# Restaurant-RFID-System.net
KiCad netlist of a schematic drawn in EAGLE
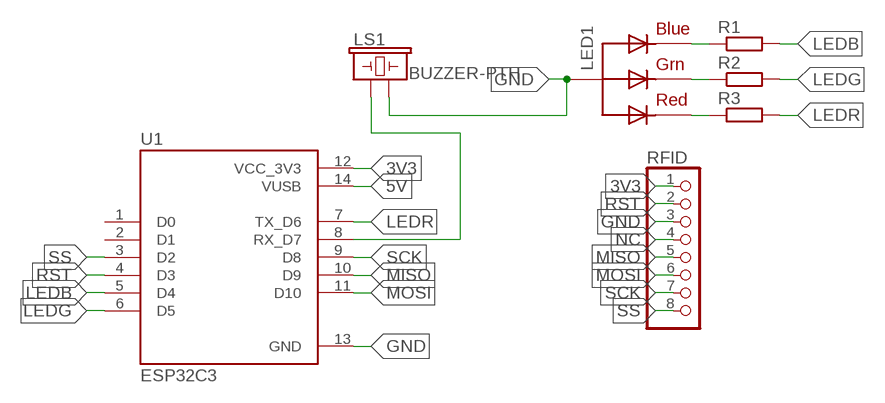
[diagram p0: schematic, sheet 1]

(export (version "E")
  (design (tool "Eeschema 10.0.6"))
  (components
    (comp (ref "LED1")
      (value "RGBLED_CA-5MM")
      (footprint "eagle-import:LED5MMRGB")
      (libsource (lib "eagle-import") (part "RGBLED_CA-5MM"))
    )
    (comp (ref "LS1")
      (value "BUZZER-PTH")
      (footprint "eagle-import:BUZZER-12MM")
      (libsource (lib "eagle-import") (part "BUZZER-PTH"))
    )
    (comp (ref "R1")
      (value "R-EU_R0805")
      (footprint "eagle-import:R0805")
      (libsource (lib "eagle-import") (part "R-EU_R0805"))
    )
    (comp (ref "R2")
      (value "R-EU_R0805")
      (footprint "eagle-import:R0805")
      (libsource (lib "eagle-import") (part "R-EU_R0805"))
    )
    (comp (ref "R3")
      (value "R-EU_R0805")
      (footprint "eagle-import:R0805")
      (libsource (lib "eagle-import") (part "R-EU_R0805"))
    )
    (comp (ref "RFID")
      (value "PINHD-1X8")
      (footprint "eagle-import:1X08")
      (libsource (lib "eagle-import") (part "PINHD-1X8"))
    )
    (comp (ref "U1")
      (value "ESP32C3")
      (footprint "eagle-import:MODULE_113991054")
      (fields (field (name "MF") "Seeed Technology Co., Ltd") (field (name "MP") "113991054"))
      (libsource (lib "eagle-import") (part "113991054"))
    )
  )
  (nets
    (net (code "1") (name "3V3") (class "Default")
      (node (ref "RFID") (pin "1") (pinfunction "1_1") (pintype "passive"))
      (node (ref "U1") (pin "12") (pinfunction "VCC_3V3_12") (pintype "power_in"))
    )
    (net (code "2") (name "5V") (class "Default")
      (node (ref "U1") (pin "14") (pinfunction "VUSB_14") (pintype "power_in"))
    )
    (net (code "3") (name "GND") (class "Default")
      (node (ref "LED1") (pin "2") (pinfunction "VCC_2") (pintype "bidirectional"))
      (node (ref "LS1") (pin "-") (pinfunction "2_-") (pintype "passive"))
      (node (ref "RFID") (pin "3") (pinfunction "3_3") (pintype "passive"))
      (node (ref "U1") (pin "13") (pinfunction "GND_13") (pintype "power_in"))
    )
    (net (code "4") (name "LEDB") (class "Default")
      (node (ref "R1") (pin "2") (pinfunction "2_2") (pintype "passive"))
      (node (ref "U1") (pin "5") (pinfunction "D4_5") (pintype "bidirectional"))
    )
    (net (code "5") (name "LEDG") (class "Default")
      (node (ref "R2") (pin "2") (pinfunction "2_2") (pintype "passive"))
      (node (ref "U1") (pin "6") (pinfunction "D5_6") (pintype "bidirectional"))
    )
    (net (code "6") (name "LEDR") (class "Default")
      (node (ref "R3") (pin "2") (pinfunction "2_2") (pintype "passive"))
      (node (ref "U1") (pin "7") (pinfunction "TX_D6_7") (pintype "bidirectional"))
    )
    (net (code "7") (name "MISO") (class "Default")
      (node (ref "RFID") (pin "5") (pinfunction "5_5") (pintype "passive"))
      (node (ref "U1") (pin "10") (pinfunction "D9_10") (pintype "bidirectional"))
    )
    (net (code "8") (name "MOSI") (class "Default")
      (node (ref "RFID") (pin "6") (pinfunction "6_6") (pintype "passive"))
      (node (ref "U1") (pin "11") (pinfunction "D10_11") (pintype "bidirectional"))
    )
    (net (code "9") (name "NC") (class "Default")
      (node (ref "RFID") (pin "4") (pinfunction "4_4") (pintype "passive"))
    )
    (net (code "10") (name "Net-(LED1-BLUE)") (class "Default")
      (node (ref "LED1") (pin "4") (pinfunction "BLUE_4") (pintype "bidirectional"))
      (node (ref "R1") (pin "1") (pinfunction "1_1") (pintype "passive"))
    )
    (net (code "11") (name "Net-(LED1-GREEN)") (class "Default")
      (node (ref "LED1") (pin "3") (pinfunction "GREEN_3") (pintype "bidirectional"))
      (node (ref "R2") (pin "1") (pinfunction "1_1") (pintype "passive"))
    )
    (net (code "12") (name "Net-(LED1-RED)") (class "Default")
      (node (ref "LED1") (pin "1") (pinfunction "RED_1") (pintype "bidirectional"))
      (node (ref "R3") (pin "1") (pinfunction "1_1") (pintype "passive"))
    )
    (net (code "13") (name "Net-(LS1-1)") (class "Default")
      (node (ref "LS1") (pin "+") (pinfunction "1_+") (pintype "passive"))
      (node (ref "U1") (pin "8") (pinfunction "RX_D7_8") (pintype "bidirectional"))
    )
    (net (code "14") (name "RST") (class "Default")
      (node (ref "RFID") (pin "2") (pinfunction "2_2") (pintype "passive"))
      (node (ref "U1") (pin "4") (pinfunction "D3_4") (pintype "bidirectional"))
    )
    (net (code "15") (name "SCK") (class "Default")
      (node (ref "RFID") (pin "7") (pinfunction "7_7") (pintype "passive"))
      (node (ref "U1") (pin "9") (pinfunction "D8_9") (pintype "bidirectional"))
    )
    (net (code "16") (name "SS") (class "Default")
      (node (ref "RFID") (pin "8") (pinfunction "8_8") (pintype "passive"))
      (node (ref "U1") (pin "3") (pinfunction "D2_3") (pintype "bidirectional"))
    )
    (net (code "17") (name "unconnected-(U1-D0-Pad1)") (class "Default")
      (node (ref "U1") (pin "1") (pinfunction "D0_1") (pintype "bidirectional"))
    )
    (net (code "18") (name "unconnected-(U1-D1-Pad2)") (class "Default")
      (node (ref "U1") (pin "2") (pinfunction "D1_2") (pintype "bidirectional"))
    )
  )
)
